# Detection.net
KiCad netlist of a schematic drawn in Altium Designer
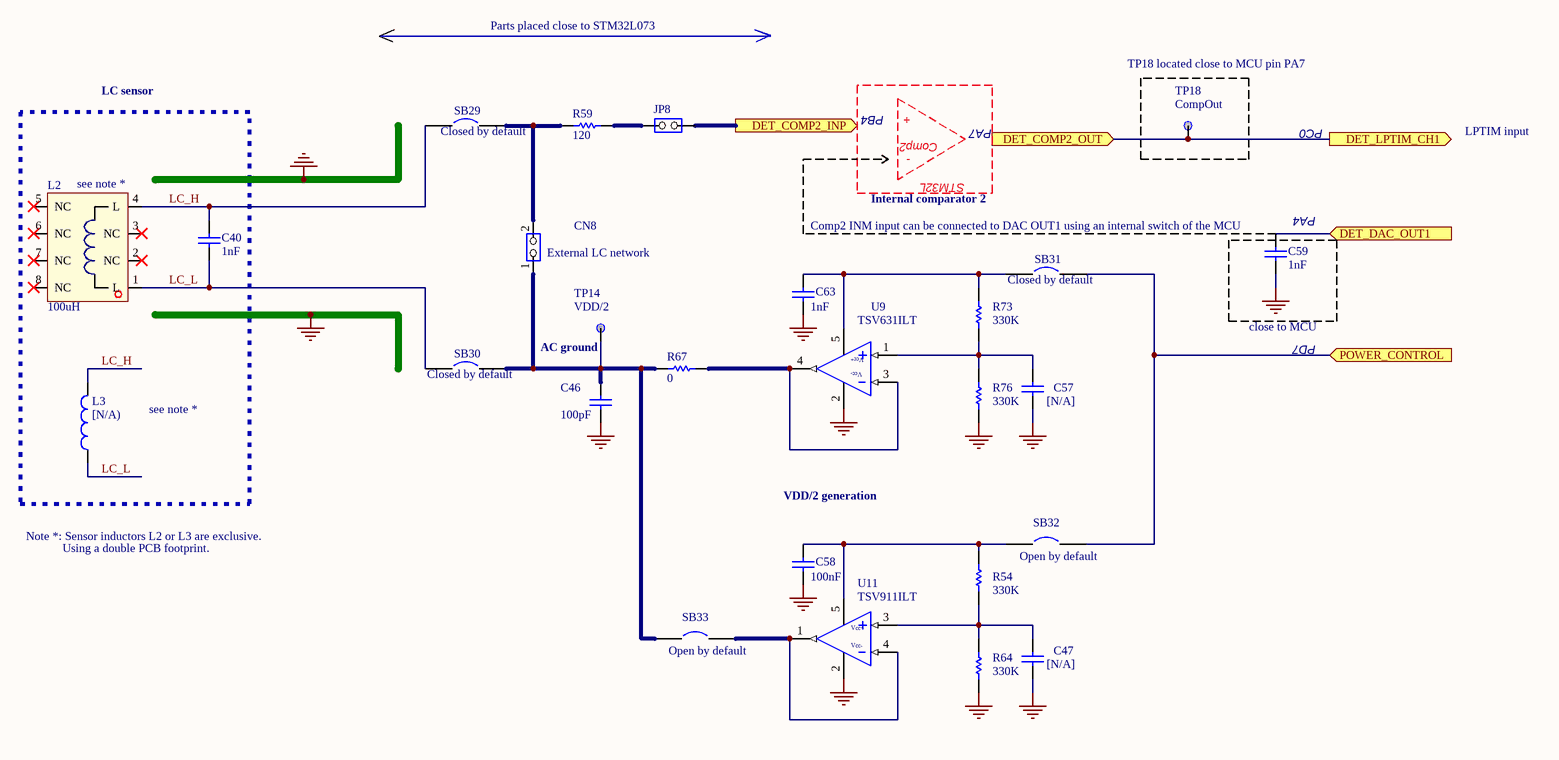
[diagram p0: Detection.SchDoc]

(export (version "E")
  (design (tool "Eeschema 10.0.6"))
  (components
    (comp (ref "C40")
      (value "1nF")
      (footprint "0603C")
      (description "Capacitor")
      (libsource (lib "MCD_TOOLS") (part "Capacitor_ST"))
    )
    (comp (ref "C46")
      (value "100pF")
      (footprint "0402C")
      (description "Capacitor")
      (libsource (lib "MCD_TOOLS") (part "Capacitor_ST"))
    )
    (comp (ref "C47")
      (value "[N/A]")
      (footprint "0603C")
      (description "Capacitor")
      (libsource (lib "MCD_TOOLS") (part "Capacitor_ST"))
    )
    (comp (ref "C57")
      (value "[N/A]")
      (footprint "0603C")
      (description "Capacitor")
      (libsource (lib "MCD_TOOLS") (part "Capacitor_ST"))
    )
    (comp (ref "C58")
      (value "100nF")
      (footprint "0402C")
      (description "Capacitor")
      (libsource (lib "MCD_TOOLS") (part "Capacitor_ST"))
    )
    (comp (ref "C59")
      (value "1nF")
      (footprint "0603C")
      (description "Capacitor")
      (libsource (lib "MCD_TOOLS") (part "Capacitor_ST"))
    )
    (comp (ref "C63")
      (value "1nF")
      (footprint "0402C")
      (description "Capacitor")
      (libsource (lib "MCD_TOOLS") (part "Capacitor_ST"))
    )
    (comp (ref "CN8")
      (value "Header 2X1")
      (footprint "SIP2")
      (fields (field (name "SILKSCREEN") "External LC network"))
      (libsource (lib "*") (part "JP2"))
    )
    (comp (ref "JP8") (value "~") (footprint "SIP2") (libsource (lib "") (part "JP2_1")))
    (comp (ref "L2")
      (value "100uH")
      (footprint "ER95")
      (description "Wurth E core inductor 750315110")
      (libsource (lib "Almos") (part "Wurth_ER9.5"))
    )
    (comp (ref "L3")
      (value "[N/A)")
      (footprint "LSM2_4R4X3R2_H3")
      (description "Cyntec/Delta  Inductor SIE4734-101")
      (fields (field (name "PUBLISHER") "Altium Limited"))
      (libsource (lib "Miscellaneous Devices") (part "Inductor"))
    )
    (comp (ref "R54")
      (value "330K")
      (footprint "0402R")
      (description "Resistor")
      (fields (field (name "PUBLISHER") "Altium Limited"))
      (libsource (lib "Miscellaneous Devices") (part "Res1"))
    )
    (comp (ref "R59")
      (value "120")
      (footprint "0603R")
      (description "Resistor")
      (fields (field (name "PUBLISHER") "Altium Limited"))
      (libsource (lib "Miscellaneous Devices") (part "Res1"))
    )
    (comp (ref "R64")
      (value "330K")
      (footprint "0402R")
      (description "Resistor")
      (fields (field (name "PUBLISHER") "Altium Limited"))
      (libsource (lib "Miscellaneous Devices") (part "Res1"))
    )
    (comp (ref "R67")
      (value "0")
      (footprint "0603R")
      (description "Resistor")
      (fields (field (name "PUBLISHER") "Altium Limited"))
      (libsource (lib "Miscellaneous Devices") (part "Res1"))
    )
    (comp (ref "R73")
      (value "330K")
      (footprint "0402R")
      (description "Resistor")
      (fields (field (name "PUBLISHER") "Altium Limited"))
      (libsource (lib "Miscellaneous Devices") (part "Res1"))
    )
    (comp (ref "R76")
      (value "330K")
      (footprint "0402R")
      (description "Resistor")
      (fields (field (name "PUBLISHER") "Altium Limited"))
      (libsource (lib "Miscellaneous Devices") (part "Res1"))
    )
    (comp (ref "SB29")
      (value "Closed by default")
      (footprint "SB_0603")
      (description "Circuit Breaker")
      (fields (field (name "PUBLISHER") "Altium Limited"))
      (libsource (lib "Miscellaneous Devices") (part "Circuit Breaker"))
    )
    (comp (ref "SB30")
      (value "Closed by default")
      (footprint "SB_0603")
      (description "Circuit Breaker")
      (fields (field (name "PUBLISHER") "Altium Limited"))
      (libsource (lib "Miscellaneous Devices") (part "Circuit Breaker"))
    )
    (comp (ref "SB31")
      (value "Closed by default")
      (footprint "SB_0603")
      (description "Circuit Breaker")
      (fields (field (name "PUBLISHER") "Altium Limited"))
      (libsource (lib "Miscellaneous Devices") (part "Circuit Breaker"))
    )
    (comp (ref "SB32")
      (value "Open by default")
      (footprint "SB_0603")
      (description "Circuit Breaker")
      (fields (field (name "PUBLISHER") "Altium Limited"))
      (libsource (lib "Miscellaneous Devices") (part "Circuit Breaker"))
    )
    (comp (ref "SB33")
      (value "Open by default")
      (footprint "SB_0603")
      (description "Circuit Breaker")
      (fields (field (name "PUBLISHER") "Altium Limited"))
      (libsource (lib "Miscellaneous Devices") (part "Circuit Breaker"))
    )
    (comp (ref "TP14")
      (value "TP")
      (footprint "TP")
      (fields (field (name "SILKSCREEN") "VDD/2"))
      (libsource (lib "*") (part "TP"))
    )
    (comp (ref "TP18")
      (value "TP")
      (footprint "TP")
      (fields (field (name "SILKSCREEN") "CompOut"))
      (libsource (lib "*") (part "TP"))
    )
    (comp (ref "U9")
      (value "TSV631ILT")
      (footprint "SOT-23-5L")
      (description "single OpAmp 60 µA, 880 kHz, 5 V CMOS")
      (libsource (lib "Almos") (part "TSV631ILT"))
    )
    (comp (ref "U11")
      (value "TSV911ILT")
      (footprint "SOT-23-5L")
      (description "single 8MHz  operational amplifiers")
      (libsource (lib "Almos") (part "TSV911ILT"))
    )
  )
  (nets
    (net (code "1") (name "/DET_COMP2_INP") (class "Default")
      (node (ref "JP8") (pin "2") (pinfunction "NO_2") (pintype "passive"))
    )
    (net (code "2") (name "/DET_COMP2_OUT") (class "Default")
      (node (ref "TP18") (pin "1") (pinfunction "1_1") (pintype "passive"))
    )
    (net (code "3") (name "/DET_DAC_OUT1") (class "Default")
      (node (ref "C59") (pin "1") (pinfunction "1_1") (pintype "passive"))
    )
    (net (code "4") (name "/LC_H") (class "Default")
      (node (ref "C40") (pin "2") (pinfunction "2_2") (pintype "passive"))
      (node (ref "L2") (pin "4") (pinfunction "L_4") (pintype "passive"))
      (node (ref "L3") (pin "2") (pinfunction "2_2") (pintype "passive"))
      (node (ref "SB29") (pin "1") (pinfunction "1_1") (pintype "passive"))
    )
    (net (code "5") (name "/LC_L") (class "Default")
      (node (ref "C40") (pin "1") (pinfunction "1_1") (pintype "passive"))
      (node (ref "L2") (pin "1") (pinfunction "L_1") (pintype "passive"))
      (node (ref "L3") (pin "1") (pinfunction "1_1") (pintype "passive"))
      (node (ref "SB30") (pin "1") (pinfunction "1_1") (pintype "passive"))
    )
    (net (code "6") (name "/POWER_CONTROL") (class "Default")
      (node (ref "SB31") (pin "2") (pinfunction "2_2") (pintype "passive"))
      (node (ref "SB32") (pin "2") (pinfunction "2_2") (pintype "passive"))
    )
    (net (code "7") (name "GND") (class "Default")
      (node (ref "C46") (pin "1") (pinfunction "1_1") (pintype "passive"))
      (node (ref "C47") (pin "2") (pinfunction "2_2") (pintype "passive"))
      (node (ref "C57") (pin "2") (pinfunction "2_2") (pintype "passive"))
      (node (ref "C58") (pin "2") (pinfunction "2_2") (pintype "passive"))
      (node (ref "C59") (pin "2") (pinfunction "2_2") (pintype "passive"))
      (node (ref "C63") (pin "2") (pinfunction "2_2") (pintype "passive"))
      (node (ref "R64") (pin "2") (pinfunction "2_2") (pintype "passive"))
      (node (ref "R76") (pin "2") (pinfunction "2_2") (pintype "passive"))
      (node (ref "U11") (pin "2") (pinfunction "Vcc-_2") (pintype "power_in"))
      (node (ref "U9") (pin "2") (pinfunction "Vcc-_2") (pintype "power_in"))
    )
    (net (code "8") (name "Net-(CN8-COMMON)") (class "Default")
      (node (ref "C46") (pin "2") (pinfunction "2_2") (pintype "passive"))
      (node (ref "CN8") (pin "1") (pinfunction "COMMON_1") (pintype "passive"))
      (node (ref "R67") (pin "1") (pinfunction "1_1") (pintype "passive"))
      (node (ref "SB30") (pin "2") (pinfunction "2_2") (pintype "passive"))
      (node (ref "SB33") (pin "1") (pinfunction "1_1") (pintype "passive"))
      (node (ref "TP14") (pin "1") (pinfunction "1_1") (pintype "passive"))
    )
    (net (code "9") (name "Net-(CN8-NO)") (class "Default")
      (node (ref "CN8") (pin "2") (pinfunction "NO_2") (pintype "passive"))
      (node (ref "R59") (pin "1") (pinfunction "1_1") (pintype "passive"))
      (node (ref "SB29") (pin "2") (pinfunction "2_2") (pintype "passive"))
    )
    (net (code "10") (name "Net-(JP8-COMMON)") (class "Default")
      (node (ref "JP8") (pin "1") (pinfunction "COMMON_1") (pintype "passive"))
      (node (ref "R59") (pin "2") (pinfunction "2_2") (pintype "passive"))
    )
    (net (code "11") (name "Net-(U9-OUT)") (class "Default")
      (node (ref "R67") (pin "2") (pinfunction "2_2") (pintype "passive"))
      (node (ref "U9") (pin "3") (pinfunction "Vm_3") (pintype "input"))
      (node (ref "U9") (pin "4") (pinfunction "OUT_4") (pintype "output"))
    )
    (net (code "12") (name "Net-(U9-Vcc+)") (class "Default")
      (node (ref "C63") (pin "1") (pinfunction "1_1") (pintype "passive"))
      (node (ref "R73") (pin "1") (pinfunction "1_1") (pintype "passive"))
      (node (ref "SB31") (pin "1") (pinfunction "1_1") (pintype "passive"))
      (node (ref "U9") (pin "5") (pinfunction "Vcc+_5") (pintype "power_in"))
    )
    (net (code "13") (name "Net-(U9-Vp)") (class "Default")
      (node (ref "C57") (pin "1") (pinfunction "1_1") (pintype "passive"))
      (node (ref "R73") (pin "2") (pinfunction "2_2") (pintype "passive"))
      (node (ref "R76") (pin "1") (pinfunction "1_1") (pintype "passive"))
      (node (ref "U9") (pin "1") (pinfunction "Vp_1") (pintype "input"))
    )
    (net (code "14") (name "Net-(U11-OUT)") (class "Default")
      (node (ref "SB33") (pin "2") (pinfunction "2_2") (pintype "passive"))
      (node (ref "U11") (pin "1") (pinfunction "OUT_1") (pintype "output"))
      (node (ref "U11") (pin "4") (pinfunction "Vm_4") (pintype "input"))
    )
    (net (code "15") (name "Net-(U11-Vcc+)") (class "Default")
      (node (ref "C58") (pin "1") (pinfunction "1_1") (pintype "passive"))
      (node (ref "R54") (pin "1") (pinfunction "1_1") (pintype "passive"))
      (node (ref "SB32") (pin "1") (pinfunction "1_1") (pintype "passive"))
      (node (ref "U11") (pin "5") (pinfunction "Vcc+_5") (pintype "power_in"))
    )
    (net (code "16") (name "Net-(U11-Vp)") (class "Default")
      (node (ref "C47") (pin "1") (pinfunction "1_1") (pintype "passive"))
      (node (ref "R54") (pin "2") (pinfunction "2_2") (pintype "passive"))
      (node (ref "R64") (pin "1") (pinfunction "1_1") (pintype "passive"))
      (node (ref "U11") (pin "3") (pinfunction "Vp_3") (pintype "input"))
    )
    (net (code "17") (name "unconnected-(L2-NC-Pad2)") (class "Default")
      (node (ref "L2") (pin "2") (pinfunction "NC_2") (pintype "passive+no_connect"))
    )
    (net (code "18") (name "unconnected-(L2-NC-Pad3)") (class "Default")
      (node (ref "L2") (pin "3") (pinfunction "NC_3") (pintype "passive+no_connect"))
    )
    (net (code "19") (name "unconnected-(L2-NC-Pad5)") (class "Default")
      (node (ref "L2") (pin "5") (pinfunction "NC_5") (pintype "passive+no_connect"))
    )
    (net (code "20") (name "unconnected-(L2-NC-Pad6)") (class "Default")
      (node (ref "L2") (pin "6") (pinfunction "NC_6") (pintype "passive+no_connect"))
    )
    (net (code "21") (name "unconnected-(L2-NC-Pad7)") (class "Default")
      (node (ref "L2") (pin "7") (pinfunction "NC_7") (pintype "passive+no_connect"))
    )
    (net (code "22") (name "unconnected-(L2-NC-Pad8)") (class "Default")
      (node (ref "L2") (pin "8") (pinfunction "NC_8") (pintype "passive+no_connect"))
    )
  )
)
